# Cargador_12_6V-5A.net
KiCad netlist of a schematic drawn in EAGLE
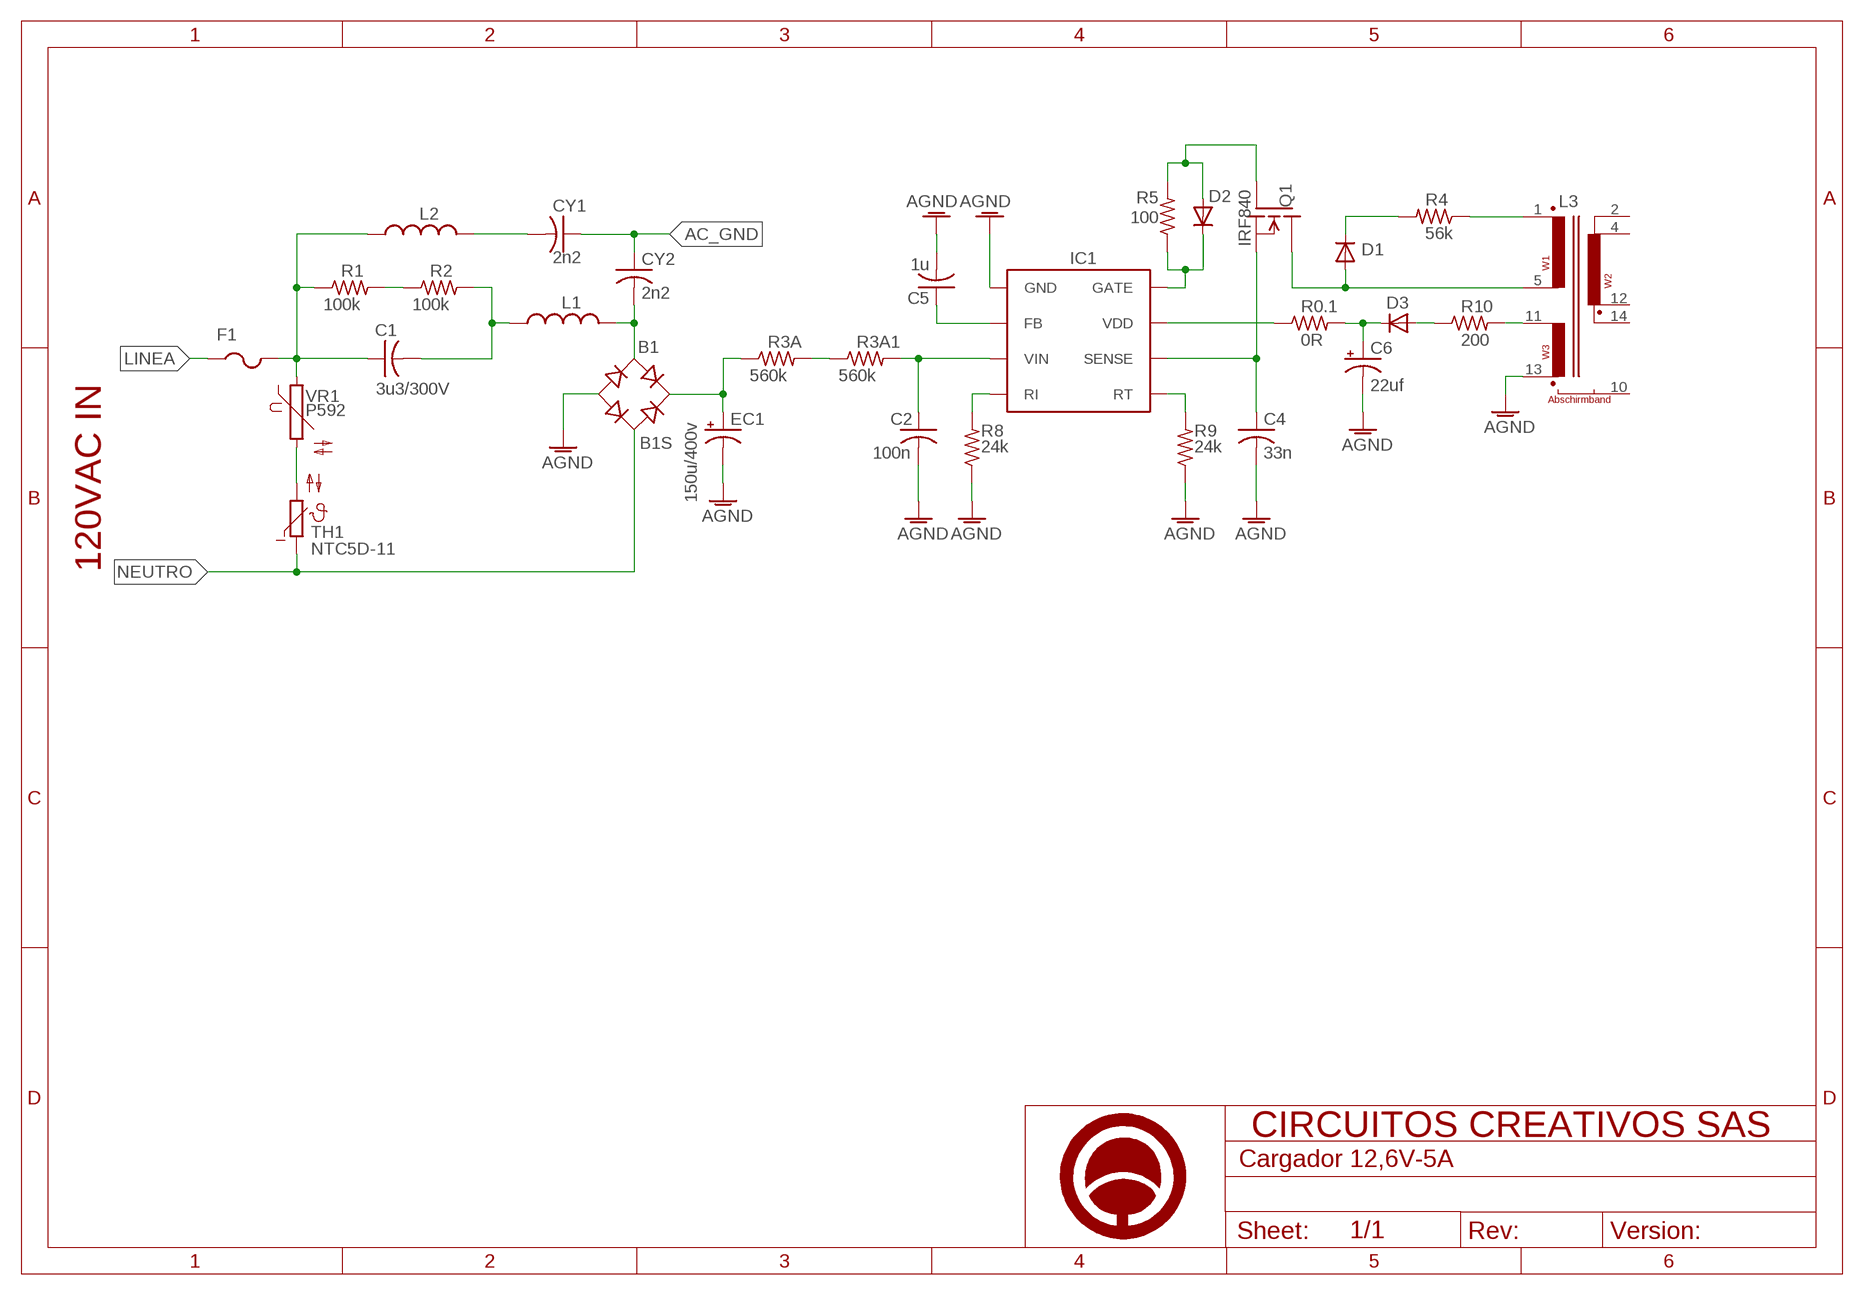
[diagram p0: schematic, sheet 1]

(export (version "E")
  (design (tool "Eeschema 10.0.6"))
  (components
    (comp (ref "B1")
      (value "B1S")
      (footprint "eagle-import:MBS")
      (libsource (lib "eagle-import") (part "BS1"))
    )
    (comp (ref "C1")
      (value "3u3/300V")
      (footprint "eagle-import:C050-024X044")
      (libsource (lib "eagle-import") (part "C-US050-024X044"))
    )
    (comp (ref "C2")
      (value "100n")
      (footprint "eagle-import:C050-024X044")
      (libsource (lib "eagle-import") (part "C-US050-024X044"))
    )
    (comp (ref "C4")
      (value "33n")
      (footprint "eagle-import:C050-024X044")
      (libsource (lib "eagle-import") (part "C-US050-024X044"))
    )
    (comp (ref "C5")
      (value "1u")
      (footprint "eagle-import:C050-024X044")
      (libsource (lib "eagle-import") (part "C-US050-024X044"))
    )
    (comp (ref "C6")
      (value "22uf")
      (footprint "eagle-import:E5-10,5")
      (libsource (lib "eagle-import") (part "CPOL-USE5-10.5"))
    )
    (comp (ref "CY1")
      (value "2n2")
      (footprint "eagle-import:C050-024X044")
      (libsource (lib "eagle-import") (part "C-US050-024X044"))
    )
    (comp (ref "CY2")
      (value "2n2")
      (footprint "eagle-import:C050-024X044")
      (libsource (lib "eagle-import") (part "C-US050-024X044"))
    )
    (comp (ref "D1")
      (value "MBR0520LT")
      (footprint "eagle-import:SOD123")
      (libsource (lib "eagle-import") (part "MBR0520LT"))
    )
    (comp (ref "D2")
      (value "MBR0520LT")
      (footprint "eagle-import:SOD123")
      (libsource (lib "eagle-import") (part "MBR0520LT"))
    )
    (comp (ref "D3")
      (value "MBR0520LT")
      (footprint "eagle-import:SOD123")
      (libsource (lib "eagle-import") (part "MBR0520LT"))
    )
    (comp (ref "EC1")
      (value "150u/400v")
      (footprint "eagle-import:E5-10,5")
      (libsource (lib "eagle-import") (part "CPOL-USE5-10.5"))
    )
    (comp (ref "F1")
      (value "PTCFUSE-1812")
      (footprint "eagle-import:1812")
      (libsource (lib "eagle-import") (part "PTCFUSE-1812"))
    )
    (comp (ref "IC1")
      (value "OB2269")
      (footprint "eagle-import:SOP-8")
      (libsource (lib "eagle-import") (part "OB2269"))
    )
    (comp (ref "L1")
      (value "L-USIR-2")
      (footprint "eagle-import:IR-2")
      (libsource (lib "eagle-import") (part "L-USIR-2"))
    )
    (comp (ref "L2")
      (value "L-USIR-2")
      (footprint "eagle-import:IR-2")
      (libsource (lib "eagle-import") (part "L-USIR-2"))
    )
    (comp (ref "L3")
      (value "ST-D4")
      (footprint "eagle-import:ST-D4")
      (libsource (lib "eagle-import") (part "ST-D4"))
    )
    (comp (ref "Q1")
      (value "IRF840")
      (footprint "eagle-import:TO220")
      (libsource (lib "eagle-import") (part "IRF840"))
    )
    (comp (ref "R0.1")
      (value "0R")
      (footprint "eagle-import:0204_7")
      (libsource (lib "eagle-import") (part "R-US_0204/7"))
    )
    (comp (ref "R1")
      (value "100k")
      (footprint "eagle-import:0204_7")
      (libsource (lib "eagle-import") (part "R-US_0204/7"))
    )
    (comp (ref "R2")
      (value "100k")
      (footprint "eagle-import:0204_7")
      (libsource (lib "eagle-import") (part "R-US_0204/7"))
    )
    (comp (ref "R3A")
      (value "560k")
      (footprint "eagle-import:0204_7")
      (libsource (lib "eagle-import") (part "R-US_0204/7"))
    )
    (comp (ref "R3A1")
      (value "560k")
      (footprint "eagle-import:0204_7")
      (libsource (lib "eagle-import") (part "R-US_0204/7"))
    )
    (comp (ref "R4")
      (value "56k")
      (footprint "eagle-import:0204_7")
      (libsource (lib "eagle-import") (part "R-US_0204/7"))
    )
    (comp (ref "R5")
      (value "100")
      (footprint "eagle-import:0204_7")
      (libsource (lib "eagle-import") (part "R-US_0204/7"))
    )
    (comp (ref "R8")
      (value "24k")
      (footprint "eagle-import:0204_7")
      (libsource (lib "eagle-import") (part "R-US_0204/7"))
    )
    (comp (ref "R9")
      (value "24k")
      (footprint "eagle-import:0204_7")
      (libsource (lib "eagle-import") (part "R-US_0204/7"))
    )
    (comp (ref "R10")
      (value "200")
      (footprint "eagle-import:0204_7")
      (libsource (lib "eagle-import") (part "R-US_0204/7"))
    )
    (comp (ref "TH1")
      (value "NTC5D-11")
      (footprint "eagle-import:N640")
      (libsource (lib "eagle-import") (part "NTC640-9"))
    )
    (comp (ref "U$1")
      (value "A4_HORIZONTAL")
      (footprint "eagle-import:LOGO")
      (libsource (lib "eagle-import") (part "A4_HORIZONTAL"))
    )
    (comp (ref "VR1")
      (value "P592")
      (footprint "eagle-import:P592")
      (libsource (lib "eagle-import") (part "P592"))
    )
  )
  (nets
    (net (code "1") (name "AC_GND") (class "Default")
      (node (ref "CY1") (pin "1") (pinfunction "1_1") (pintype "passive"))
      (node (ref "CY2") (pin "1") (pinfunction "1_1") (pintype "passive"))
    )
    (net (code "2") (name "AGND") (class "Default")
      (node (ref "B1") (pin "-") (pinfunction "-_-") (pintype "passive"))
      (node (ref "C2") (pin "2") (pinfunction "2_2") (pintype "passive"))
      (node (ref "C4") (pin "2") (pinfunction "2_2") (pintype "passive"))
      (node (ref "C5") (pin "2") (pinfunction "2_2") (pintype "passive"))
      (node (ref "C6") (pin "-") (pinfunction "-_-") (pintype "passive"))
      (node (ref "EC1") (pin "-") (pinfunction "-_-") (pintype "passive"))
      (node (ref "IC1") (pin "GND") (pinfunction "GND_GND") (pintype "power_in"))
      (node (ref "L3") (pin "13") (pinfunction "3A_13") (pintype "passive"))
      (node (ref "R8") (pin "1") (pinfunction "1_1") (pintype "passive"))
      (node (ref "R9") (pin "1") (pinfunction "1_1") (pintype "passive"))
    )
    (net (code "3") (name "LINEA") (class "Default")
      (node (ref "F1") (pin "1") (pinfunction "1_1") (pintype "passive"))
    )
    (net (code "4") (name "NEUTRO") (class "Default")
      (node (ref "B1") (pin "AC2") (pinfunction "AC2_AC2") (pintype "passive"))
      (node (ref "TH1") (pin "1") (pinfunction "1_1") (pintype "passive"))
    )
    (net (code "5") (name "Net-(B1-Pad+)") (class "Default")
      (node (ref "B1") (pin "+") (pinfunction "+_+") (pintype "passive"))
      (node (ref "EC1") (pin "+") (pinfunction "+_+") (pintype "passive"))
      (node (ref "R3A") (pin "1") (pinfunction "1_1") (pintype "passive"))
    )
    (net (code "6") (name "Net-(B1-PadAC1)") (class "Default")
      (node (ref "B1") (pin "AC1") (pinfunction "AC1_AC1") (pintype "passive"))
      (node (ref "CY2") (pin "2") (pinfunction "2_2") (pintype "passive"))
      (node (ref "L1") (pin "2") (pinfunction "2_2") (pintype "passive"))
    )
    (net (code "7") (name "Net-(C1-Pad1)") (class "Default")
      (node (ref "C1") (pin "1") (pinfunction "1_1") (pintype "passive"))
      (node (ref "F1") (pin "2") (pinfunction "2_2") (pintype "passive"))
      (node (ref "L2") (pin "1") (pinfunction "1_1") (pintype "passive"))
      (node (ref "R1") (pin "1") (pinfunction "1_1") (pintype "passive"))
      (node (ref "VR1") (pin "1") (pinfunction "1_1") (pintype "passive"))
    )
    (net (code "8") (name "Net-(C1-Pad2)") (class "Default")
      (node (ref "C1") (pin "2") (pinfunction "2_2") (pintype "passive"))
      (node (ref "L1") (pin "1") (pinfunction "1_1") (pintype "passive"))
      (node (ref "R2") (pin "2") (pinfunction "2_2") (pintype "passive"))
    )
    (net (code "9") (name "Net-(C2-Pad1)") (class "Default")
      (node (ref "C2") (pin "1") (pinfunction "1_1") (pintype "passive"))
      (node (ref "IC1") (pin "VIN") (pinfunction "VIN_VIN") (pintype "bidirectional"))
      (node (ref "R3A1") (pin "2") (pinfunction "2_2") (pintype "passive"))
    )
    (net (code "10") (name "Net-(C5-Pad1)") (class "Default")
      (node (ref "C5") (pin "1") (pinfunction "1_1") (pintype "passive"))
      (node (ref "IC1") (pin "FB") (pinfunction "FB_FB") (pintype "bidirectional"))
    )
    (net (code "11") (name "Net-(C6-Pad+)") (class "Default")
      (node (ref "C6") (pin "+") (pinfunction "+_+") (pintype "passive"))
      (node (ref "D3") (pin "C") (pinfunction "C_C") (pintype "passive"))
      (node (ref "R0.1") (pin "2") (pinfunction "2_2") (pintype "passive"))
    )
    (net (code "12") (name "Net-(CY1-Pad2)") (class "Default")
      (node (ref "CY1") (pin "2") (pinfunction "2_2") (pintype "passive"))
      (node (ref "L2") (pin "2") (pinfunction "2_2") (pintype "passive"))
    )
    (net (code "13") (name "Net-(D1-PadC)") (class "Default")
      (node (ref "D1") (pin "C") (pinfunction "C_C") (pintype "passive"))
      (node (ref "R4") (pin "2") (pinfunction "2_2") (pintype "passive"))
    )
    (net (code "14") (name "Net-(D2-PadC)") (class "Default")
      (node (ref "D2") (pin "C") (pinfunction "C_C") (pintype "passive"))
      (node (ref "IC1") (pin "GATE") (pinfunction "GATE_GATE") (pintype "bidirectional"))
      (node (ref "R5") (pin "1") (pinfunction "1_1") (pintype "passive"))
    )
    (net (code "15") (name "Net-(D3-PadA)") (class "Default")
      (node (ref "D3") (pin "A") (pinfunction "A_A") (pintype "passive"))
      (node (ref "R10") (pin "1") (pinfunction "1_1") (pintype "passive"))
    )
    (net (code "16") (name "Net-(IC1-PadRI)") (class "Default")
      (node (ref "IC1") (pin "RI") (pinfunction "RI_RI") (pintype "bidirectional"))
      (node (ref "R8") (pin "2") (pinfunction "2_2") (pintype "passive"))
    )
    (net (code "17") (name "Net-(IC1-PadRT)") (class "Default")
      (node (ref "IC1") (pin "RT") (pinfunction "RT_RT") (pintype "bidirectional"))
      (node (ref "R9") (pin "2") (pinfunction "2_2") (pintype "passive"))
    )
    (net (code "18") (name "Net-(IC1-PadVDD)") (class "Default")
      (node (ref "IC1") (pin "VDD") (pinfunction "VDD_VDD") (pintype "power_in"))
      (node (ref "R0.1") (pin "1") (pinfunction "1_1") (pintype "passive"))
    )
    (net (code "19") (name "Net-(L3-1A)") (class "Default")
      (node (ref "L3") (pin "1") (pinfunction "1A_1") (pintype "passive"))
      (node (ref "R4") (pin "1") (pinfunction "1_1") (pintype "passive"))
    )
    (net (code "20") (name "Net-(L3-1E)") (class "Default")
      (node (ref "D1") (pin "A") (pinfunction "A_A") (pintype "passive"))
      (node (ref "L3") (pin "5") (pinfunction "1E_5") (pintype "passive"))
      (node (ref "Q1") (pin "2") (pinfunction "D_2") (pintype "passive"))
    )
    (net (code "21") (name "Net-(L3-3E)") (class "Default")
      (node (ref "L3") (pin "11") (pinfunction "3E_11") (pintype "passive"))
      (node (ref "R10") (pin "2") (pinfunction "2_2") (pintype "passive"))
    )
    (net (code "22") (name "Net-(Q1-G)") (class "Default")
      (node (ref "D2") (pin "A") (pinfunction "A_A") (pintype "passive"))
      (node (ref "Q1") (pin "1") (pinfunction "G_1") (pintype "passive"))
      (node (ref "R5") (pin "2") (pinfunction "2_2") (pintype "passive"))
    )
    (net (code "23") (name "Net-(Q1-S)") (class "Default")
      (node (ref "C4") (pin "1") (pinfunction "1_1") (pintype "passive"))
      (node (ref "IC1") (pin "SENSE") (pinfunction "SENSE_SENSE") (pintype "bidirectional"))
      (node (ref "Q1") (pin "3") (pinfunction "S_3") (pintype "passive"))
    )
    (net (code "24") (name "Net-(R1-Pad2)") (class "Default")
      (node (ref "R1") (pin "2") (pinfunction "2_2") (pintype "passive"))
      (node (ref "R2") (pin "1") (pinfunction "1_1") (pintype "passive"))
    )
    (net (code "25") (name "Net-(R3A-Pad2)") (class "Default")
      (node (ref "R3A") (pin "2") (pinfunction "2_2") (pintype "passive"))
      (node (ref "R3A1") (pin "1") (pinfunction "1_1") (pintype "passive"))
    )
    (net (code "26") (name "Net-(TH1-Pad2)") (class "Default")
      (node (ref "TH1") (pin "2") (pinfunction "2_2") (pintype "passive"))
      (node (ref "VR1") (pin "2") (pinfunction "2_2") (pintype "passive"))
    )
    (net (code "27") (name "unconnected-(L3-2A-Pad12)") (class "Default")
      (node (ref "L3") (pin "12") (pinfunction "2A_12") (pintype "passive"))
    )
    (net (code "28") (name "unconnected-(L3-2A1-Pad14)") (class "Default")
      (node (ref "L3") (pin "14") (pinfunction "2A1_14") (pintype "passive"))
    )
    (net (code "29") (name "unconnected-(L3-2E-Pad2)") (class "Default")
      (node (ref "L3") (pin "2") (pinfunction "2E_2") (pintype "passive"))
    )
    (net (code "30") (name "unconnected-(L3-2E1-Pad4)") (class "Default")
      (node (ref "L3") (pin "4") (pinfunction "2E1_4") (pintype "passive"))
    )
    (net (code "31") (name "unconnected-(L3-SCH-Pad10)") (class "Default")
      (node (ref "L3") (pin "10") (pinfunction "SCH_10") (pintype "passive"))
    )
  )
)
